# pH-ver1.net
KiCad netlist of a schematic drawn in EAGLE
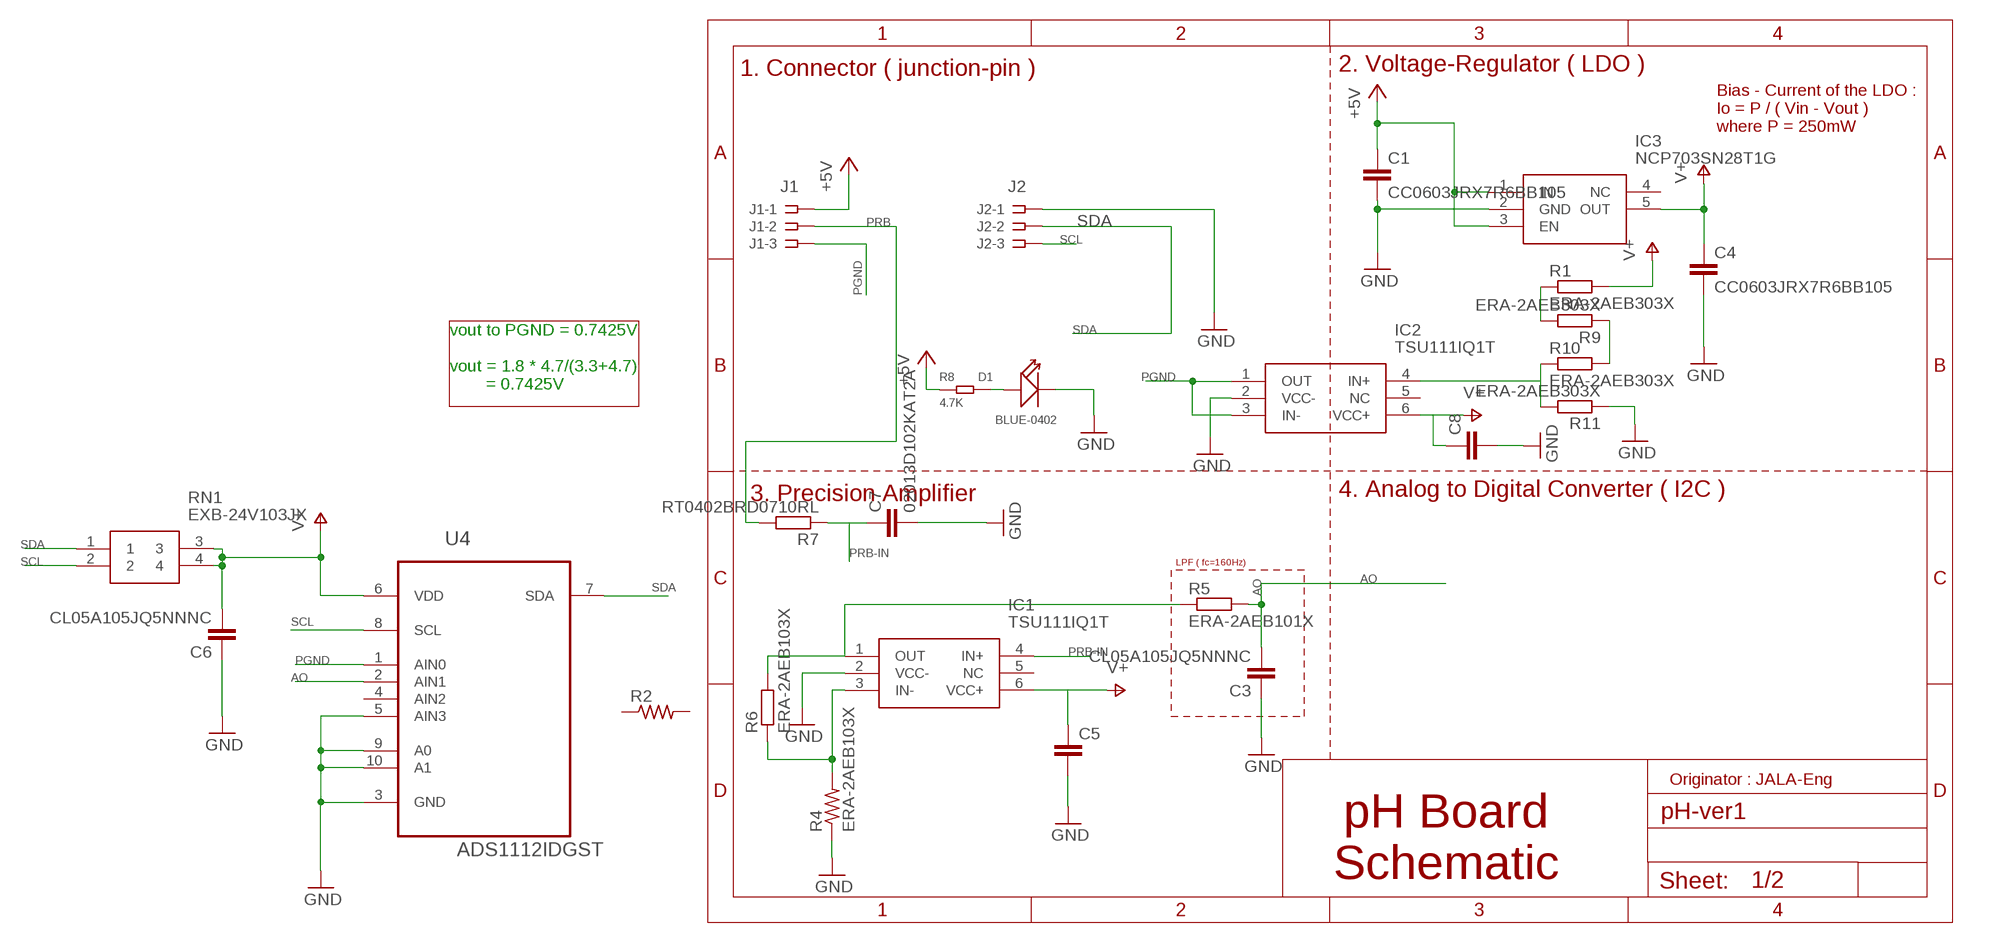
[diagram p0: schematic, sheet 1]
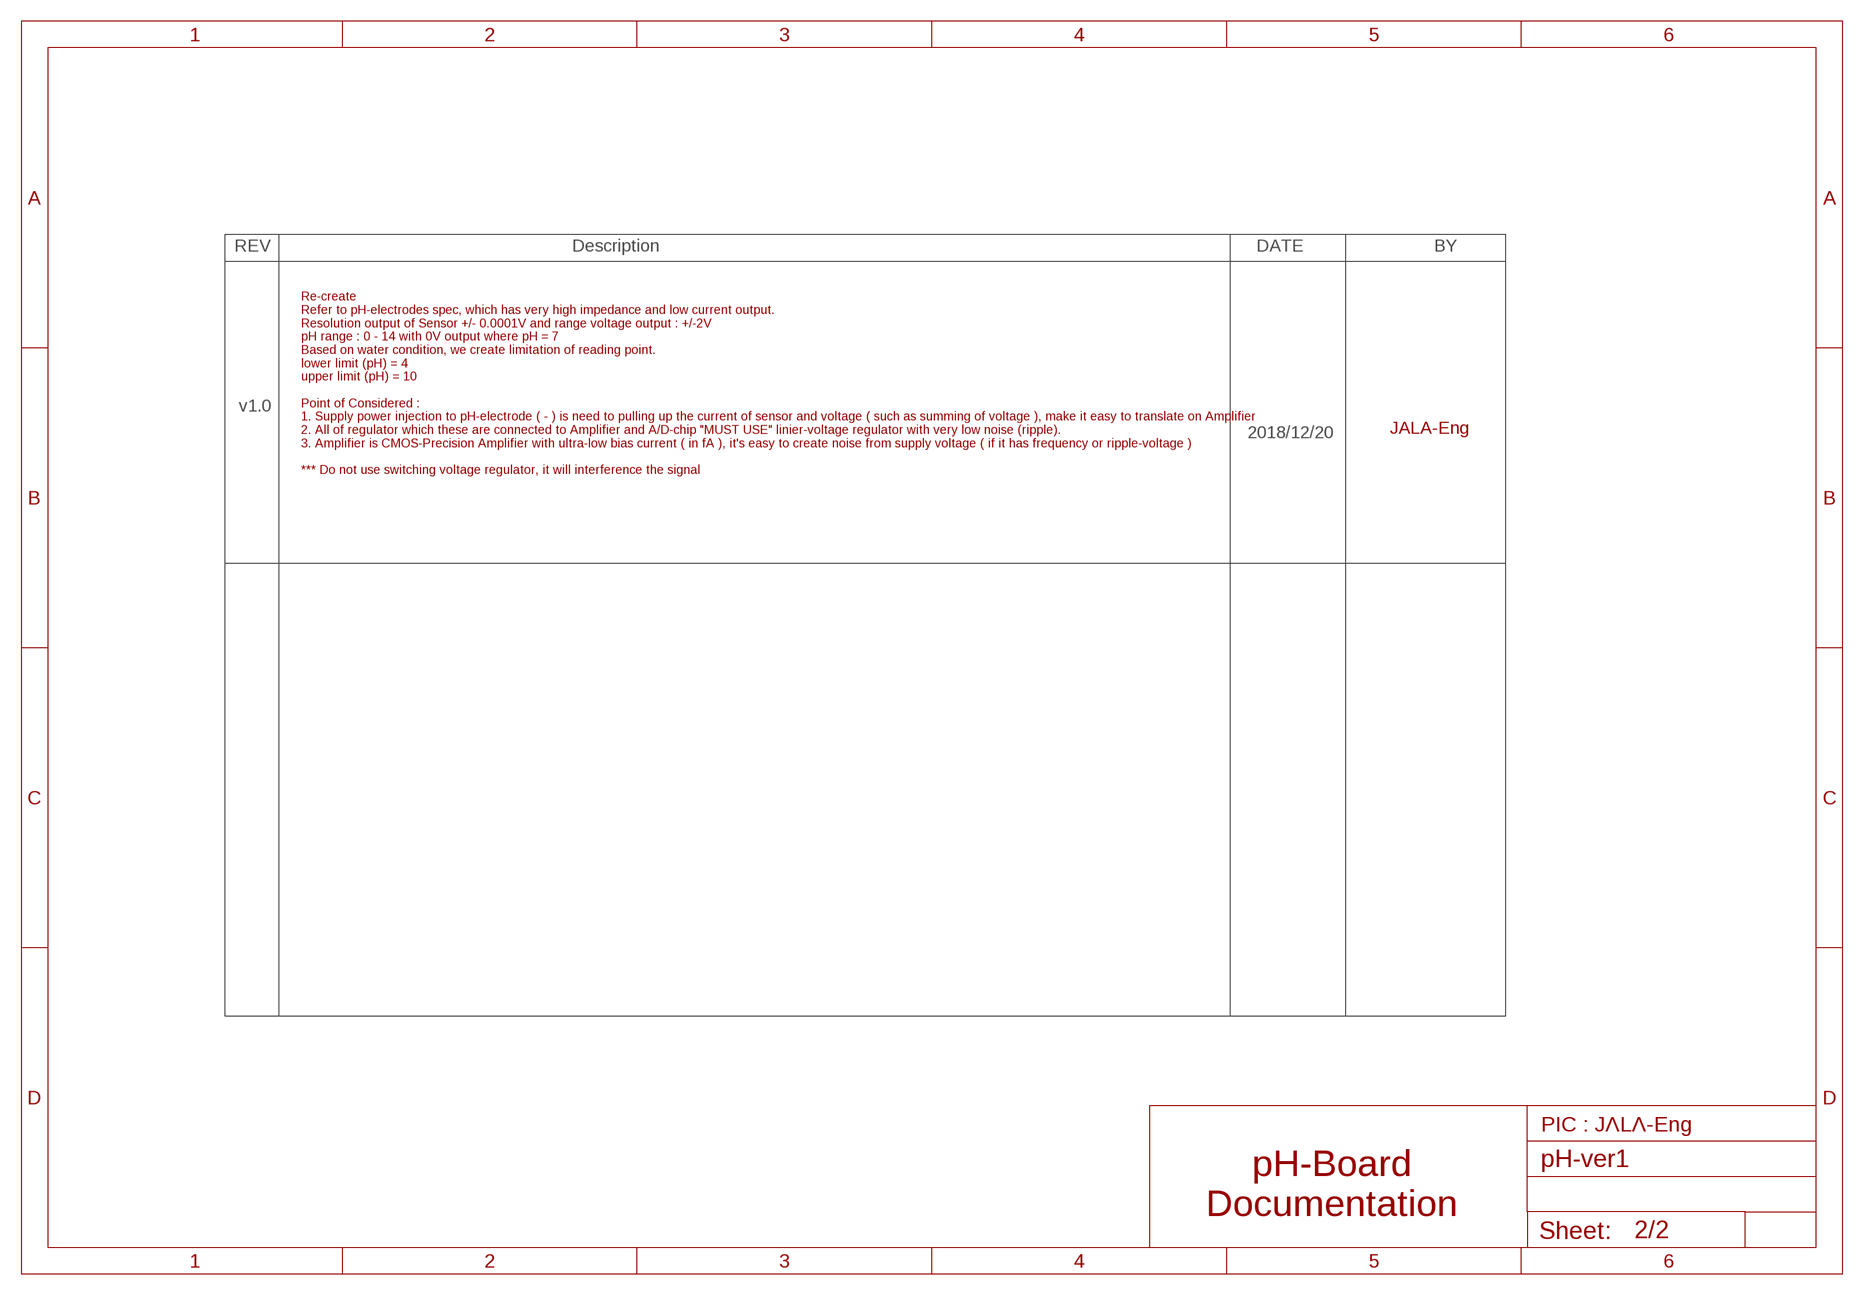
[diagram p1: schematic, sheet 2]

(export (version "E")
  (design (tool "Eeschema 10.0.6"))
  (components
    (comp (ref "C1")
      (value "CC0603JRX7R6BB105")
      (footprint "eagle-import:C0603")
      (libsource (lib "eagle-import") (part "C-EUC0603"))
    )
    (comp (ref "C3")
      (value "CL05A105JQ5NNNC")
      (footprint "eagle-import:C0402")
      (libsource (lib "eagle-import") (part "C-EUC0402"))
    )
    (comp (ref "C4")
      (value "CC0603JRX7R6BB105")
      (footprint "eagle-import:C0603")
      (libsource (lib "eagle-import") (part "C-EUC0603"))
    )
    (comp (ref "C5")
      (value "C-EUC0402")
      (footprint "eagle-import:C0402")
      (libsource (lib "eagle-import") (part "C-EUC0402"))
    )
    (comp (ref "C6")
      (value "CL05A105JQ5NNNC")
      (footprint "eagle-import:C0402")
      (libsource (lib "eagle-import") (part "C-EUC0402"))
    )
    (comp (ref "C7")
      (value "02013D102KAT2A")
      (footprint "eagle-import:C0402")
      (libsource (lib "eagle-import") (part "C-EUC0402"))
    )
    (comp (ref "C8")
      (value "C-EUC0402")
      (footprint "eagle-import:C0402")
      (libsource (lib "eagle-import") (part "C-EUC0402"))
    )
    (comp (ref "D1")
      (value "BLUE-0402")
      (footprint "eagle-import:LED-0402")
      (fields (field (name "MPN") "BL-HB337A-AV-TRB"))
      (libsource (lib "eagle-import") (part "SMD-LED-CLEAR-BLUE(0402)"))
    )
    (comp (ref "IC1")
      (value "TSU111IQ1T")
      (footprint "eagle-import:TSU111IQ1T")
      (fields (field (name "MOUSER_PART_NUMBER") "511-TSU111IQ1T") (field (name "RS_PART_NUMBER") "1623657"))
      (libsource (lib "eagle-import") (part "TSU111IQ1T"))
    )
    (comp (ref "IC2")
      (value "TSU111IQ1T")
      (footprint "eagle-import:TSU111IQ1T")
      (fields (field (name "MOUSER_PART_NUMBER") "511-TSU111IQ1T") (field (name "RS_PART_NUMBER") "1623657"))
      (libsource (lib "eagle-import") (part "TSU111IQ1T"))
    )
    (comp (ref "IC3")
      (value "NCP703SN28T1G")
      (footprint "eagle-import:SOT95P275X110-5N")
      (fields
        (field (name "MOUSER_PART_NUMBER") "863-NCP703SN28T1G")
        (field (name "RS_PART_NUMBER") "8270566P")
      )
      (libsource (lib "eagle-import") (part "NCP703SN28T1G"))
    )
    (comp (ref "J1")
      (value "J1")
      (footprint "eagle-import:SSW-103-02-S-S")
      (fields (field (name "MPN") "SSW-103-02-S-S"))
      (libsource (lib "eagle-import") (part "SSW-103-02-S-S"))
    )
    (comp (ref "J2")
      (value "J2")
      (footprint "eagle-import:SSW-103-02-S-S")
      (fields (field (name "MPN") "SSW-103-02-S-S"))
      (libsource (lib "eagle-import") (part "SSW-103-02-S-S"))
    )
    (comp (ref "R1")
      (value "ERA-2AEB303X")
      (footprint "eagle-import:R0402")
      (libsource (lib "eagle-import") (part "R-EU_R0402"))
    )
    (comp (ref "R2")
      (value "R-US_R0201")
      (footprint "eagle-import:R0201")
      (libsource (lib "eagle-import") (part "R-US_R0201"))
    )
    (comp (ref "R4")
      (value "ERA-2AEB103X")
      (footprint "eagle-import:R0201")
      (libsource (lib "eagle-import") (part "R-US_R0201"))
    )
    (comp (ref "R5")
      (value "ERA-2AEB101X")
      (footprint "eagle-import:R0402")
      (libsource (lib "eagle-import") (part "R-EU_R0402"))
    )
    (comp (ref "R6")
      (value "ERA-2AEB103X")
      (footprint "eagle-import:R0402")
      (libsource (lib "eagle-import") (part "R-EU_R0402"))
    )
    (comp (ref "R7")
      (value "RT0402BRD0710RL")
      (footprint "eagle-import:R0402")
      (libsource (lib "eagle-import") (part "R-EU_R0402"))
    )
    (comp (ref "R8")
      (value "4.7K")
      (footprint "eagle-import:R0402")
      (fields (field (name "MPN") "RC0402JR-074K7L"))
      (libsource (lib "eagle-import") (part "SMD-RES-4.7K-5%-1/16W(0402)"))
    )
    (comp (ref "R9")
      (value "ERA-2AEB303X")
      (footprint "eagle-import:R0402")
      (libsource (lib "eagle-import") (part "R-EU_R0402"))
    )
    (comp (ref "R10")
      (value "ERA-2AEB303X")
      (footprint "eagle-import:R0402")
      (libsource (lib "eagle-import") (part "R-EU_R0402"))
    )
    (comp (ref "R11")
      (value "ERA-2AEB303X")
      (footprint "eagle-import:R0402")
      (libsource (lib "eagle-import") (part "R-EU_R0402"))
    )
    (comp (ref "RN1")
      (value "EXB-24V103JX")
      (footprint "eagle-import:EXB24V102JX")
      (fields (field (name "MOUSER_PART_NUMBER") "667-EXB-24V103JX"))
      (libsource (lib "eagle-import") (part "EXB-24V103JX"))
    )
    (comp (ref "U4")
      (value "ADS1112IDGST")
      (footprint "eagle-import:SOP50P490X110-10N")
      (fields (field (name "MF") "Texas Instruments"))
      (libsource (lib "eagle-import") (part "ADS1112IDGST"))
    )
  )
  (nets
    (net (code "1") (name "+5V") (class "Default")
      (node (ref "C1") (pin "1") (pinfunction "1_1") (pintype "passive"))
      (node (ref "IC3") (pin "1") (pinfunction "IN_1") (pintype "input"))
      (node (ref "IC3") (pin "3") (pinfunction "EN_3") (pintype "bidirectional"))
      (node (ref "J1") (pin "1") (pinfunction "1_1") (pintype "passive"))
      (node (ref "R8") (pin "1") (pinfunction "1_1") (pintype "passive"))
    )
    (net (code "2") (name "AO") (class "Default")
      (node (ref "C3") (pin "2") (pinfunction "2_2") (pintype "passive"))
      (node (ref "R5") (pin "2") (pinfunction "2_2") (pintype "passive"))
      (node (ref "U4") (pin "2") (pinfunction "AIN1_2") (pintype "input"))
    )
    (net (code "3") (name "GND") (class "Default")
      (node (ref "C1") (pin "2") (pinfunction "2_2") (pintype "passive"))
      (node (ref "C3") (pin "1") (pinfunction "1_1") (pintype "passive"))
      (node (ref "C4") (pin "2") (pinfunction "2_2") (pintype "passive"))
      (node (ref "C5") (pin "2") (pinfunction "2_2") (pintype "passive"))
      (node (ref "C6") (pin "1") (pinfunction "1_1") (pintype "passive"))
      (node (ref "C7") (pin "2") (pinfunction "2_2") (pintype "passive"))
      (node (ref "C8") (pin "2") (pinfunction "2_2") (pintype "passive"))
      (node (ref "D1") (pin "-") (pinfunction "-_-") (pintype "passive"))
      (node (ref "IC1") (pin "2") (pinfunction "VCC-_2") (pintype "bidirectional"))
      (node (ref "IC2") (pin "2") (pinfunction "VCC-_2") (pintype "bidirectional"))
      (node (ref "IC3") (pin "2") (pinfunction "GND_2") (pintype "power_in"))
      (node (ref "J2") (pin "1") (pinfunction "1_1") (pintype "passive"))
      (node (ref "R11") (pin "1") (pinfunction "1_1") (pintype "passive"))
      (node (ref "R4") (pin "1") (pinfunction "1_1") (pintype "passive"))
      (node (ref "U4") (pin "10") (pinfunction "A1_10") (pintype "input"))
      (node (ref "U4") (pin "3") (pinfunction "GND_3") (pintype "passive"))
      (node (ref "U4") (pin "5") (pinfunction "AIN3_5") (pintype "input"))
      (node (ref "U4") (pin "9") (pinfunction "A0_9") (pintype "input"))
    )
    (net (code "4") (name "Net-(D1-Pad+)") (class "Default")
      (node (ref "D1") (pin "+") (pinfunction "+_+") (pintype "passive"))
      (node (ref "R8") (pin "2") (pinfunction "2_2") (pintype "passive"))
    )
    (net (code "5") (name "Net-(IC1-IN-)") (class "Default")
      (node (ref "IC1") (pin "3") (pinfunction "IN-_3") (pintype "bidirectional"))
      (node (ref "R4") (pin "2") (pinfunction "2_2") (pintype "passive"))
      (node (ref "R6") (pin "1") (pinfunction "1_1") (pintype "passive"))
    )
    (net (code "6") (name "Net-(IC1-OUT)") (class "Default")
      (node (ref "IC1") (pin "1") (pinfunction "OUT_1") (pintype "bidirectional"))
      (node (ref "R5") (pin "1") (pinfunction "1_1") (pintype "passive"))
      (node (ref "R6") (pin "2") (pinfunction "2_2") (pintype "passive"))
    )
    (net (code "7") (name "Net-(IC2-IN+)") (class "Default")
      (node (ref "IC2") (pin "4") (pinfunction "IN+_4") (pintype "bidirectional"))
      (node (ref "R10") (pin "1") (pinfunction "1_1") (pintype "passive"))
      (node (ref "R11") (pin "2") (pinfunction "2_2") (pintype "passive"))
    )
    (net (code "8") (name "Net-(R1-Pad1)") (class "Default")
      (node (ref "R1") (pin "1") (pinfunction "1_1") (pintype "passive"))
      (node (ref "R9") (pin "2") (pinfunction "2_2") (pintype "passive"))
    )
    (net (code "9") (name "Net-(R10-Pad2)") (class "Default")
      (node (ref "R10") (pin "2") (pinfunction "2_2") (pintype "passive"))
      (node (ref "R9") (pin "1") (pinfunction "1_1") (pintype "passive"))
    )
    (net (code "10") (name "PGND") (class "Default")
      (node (ref "IC2") (pin "1") (pinfunction "OUT_1") (pintype "bidirectional"))
      (node (ref "IC2") (pin "3") (pinfunction "IN-_3") (pintype "bidirectional"))
      (node (ref "J1") (pin "3") (pinfunction "1_3") (pintype "passive"))
      (node (ref "U4") (pin "1") (pinfunction "AIN0_1") (pintype "input"))
    )
    (net (code "11") (name "PRB") (class "Default")
      (node (ref "J1") (pin "2") (pinfunction "1_2") (pintype "passive"))
      (node (ref "R7") (pin "2") (pinfunction "2_2") (pintype "passive"))
    )
    (net (code "12") (name "PRB-IN") (class "Default")
      (node (ref "C7") (pin "1") (pinfunction "1_1") (pintype "passive"))
      (node (ref "IC1") (pin "4") (pinfunction "IN+_4") (pintype "bidirectional"))
      (node (ref "R7") (pin "1") (pinfunction "1_1") (pintype "passive"))
    )
    (net (code "13") (name "SCL") (class "Default")
      (node (ref "J2") (pin "3") (pinfunction "1_3") (pintype "passive"))
      (node (ref "RN1") (pin "2") (pinfunction "2_2") (pintype "bidirectional"))
      (node (ref "U4") (pin "8") (pinfunction "SCL_8") (pintype "input"))
    )
    (net (code "14") (name "SDA") (class "Default")
      (node (ref "J2") (pin "2") (pinfunction "1_2") (pintype "passive"))
      (node (ref "RN1") (pin "1") (pinfunction "1_1") (pintype "bidirectional"))
      (node (ref "U4") (pin "7") (pinfunction "SDA_7") (pintype "output"))
    )
    (net (code "15") (name "V+") (class "Default")
      (node (ref "C4") (pin "1") (pinfunction "1_1") (pintype "passive"))
      (node (ref "C5") (pin "1") (pinfunction "1_1") (pintype "passive"))
      (node (ref "C6") (pin "2") (pinfunction "2_2") (pintype "passive"))
      (node (ref "C8") (pin "1") (pinfunction "1_1") (pintype "passive"))
      (node (ref "IC1") (pin "6") (pinfunction "VCC+_6") (pintype "bidirectional"))
      (node (ref "IC2") (pin "6") (pinfunction "VCC+_6") (pintype "bidirectional"))
      (node (ref "IC3") (pin "5") (pinfunction "OUT_5") (pintype "output"))
      (node (ref "R1") (pin "2") (pinfunction "2_2") (pintype "passive"))
      (node (ref "RN1") (pin "3") (pinfunction "3_3") (pintype "bidirectional"))
      (node (ref "RN1") (pin "4") (pinfunction "4_4") (pintype "bidirectional"))
      (node (ref "U4") (pin "6") (pinfunction "VDD_6") (pintype "power_in"))
    )
    (net (code "16") (name "unconnected-(IC1-NC-Pad5)") (class "Default")
      (node (ref "IC1") (pin "5") (pinfunction "NC_5") (pintype "no_connect"))
    )
    (net (code "17") (name "unconnected-(IC2-NC-Pad5)") (class "Default")
      (node (ref "IC2") (pin "5") (pinfunction "NC_5") (pintype "no_connect"))
    )
    (net (code "18") (name "unconnected-(IC3-NC-Pad4)") (class "Default")
      (node (ref "IC3") (pin "4") (pinfunction "NC_4") (pintype "no_connect"))
    )
    (net (code "19") (name "unconnected-(R2-Pad1)") (class "Default")
      (node (ref "R2") (pin "1") (pinfunction "1_1") (pintype "passive"))
    )
    (net (code "20") (name "unconnected-(R2-Pad2)") (class "Default")
      (node (ref "R2") (pin "2") (pinfunction "2_2") (pintype "passive"))
    )
    (net (code "21") (name "unconnected-(U4-AIN2-Pad4)") (class "Default")
      (node (ref "U4") (pin "4") (pinfunction "AIN2_4") (pintype "input"))
    )
  )
)
